# USB-HOST.net
KiCad netlist of a schematic drawn in Altium Designer
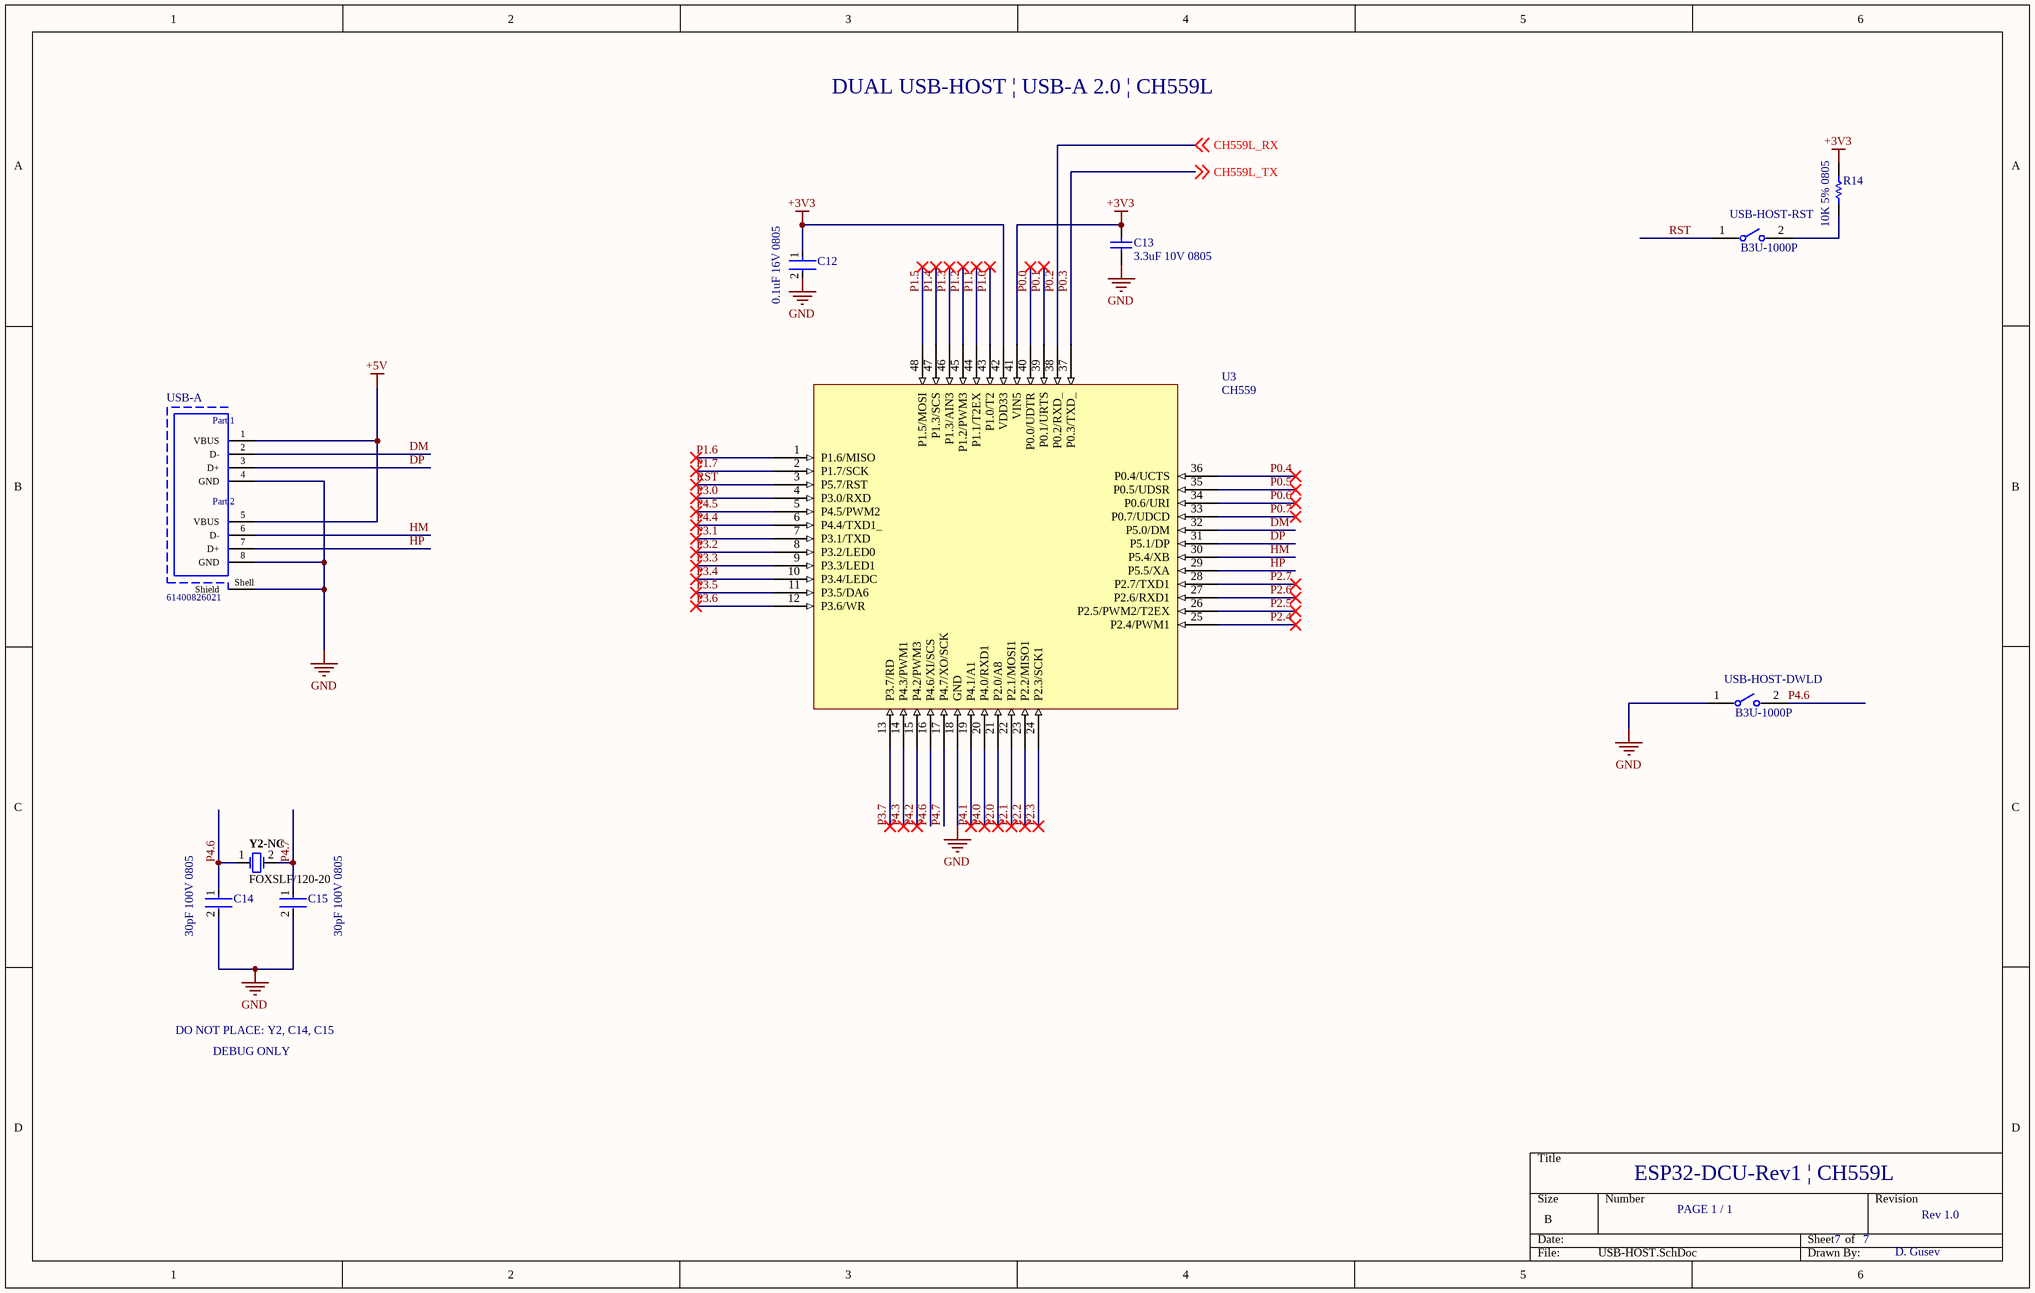
[diagram p0: USB-HOST.SchDoc]

(export (version "E")
  (design (tool "Eeschema 10.0.6"))
  (components
    (comp (ref "C12")
      (value "0.1uF 16V 0805")
      (footprint "FP-C0805C-DN-MFG")
      (description "CAP CER 0.1UF 50V X7R 0805")
      (fields
        (field (name "MANUFACTURER PART NUMBER") "C0805C104K5RACTU")
        (field (name "MANUFACTURER") "KEMET")
      )
      (libsource (lib "Altium Content Vault") (part "b4654b650e69147ec39a6b967a45e02"))
    )
    (comp (ref "C13")
      (value "3.3uF 10V 0805")
      (footprint "CAPC2013X140X50LL20T25")
      (fields
        (field (name "PART NUMBER") "0805ZD335KAT2A")
        (field (name "MANUFACTURER") "AVX Interconnect / Elco")
      )
      (libsource (lib "Altium Content Vault") (part "CAP"))
    )
    (comp (ref "C14")
      (value "30pF 100V 0805")
      (footprint "FP-C0805C-DN-MFG")
      (description "CAP CER 22PF 100V 5% NP0 0805")
      (fields
        (field (name "OCTOPART") "https://octopart.com/c0805c220j1gactu-kemet-3791395")
        (field (name "TOLERANCE") "0.05")
      )
      (libsource (lib "Altium Content Vault") (part "b4654b650e69147ec39a6b967a45e02"))
    )
    (comp (ref "C15")
      (value "30pF 100V 0805")
      (footprint "FP-C0805C-DN-MFG")
      (description "CAP CER 22PF 100V 5% NP0 0805")
      (fields
        (field (name "OCTOPART") "https://octopart.com/c0805c220j1gactu-kemet-3791395")
        (field (name "TOLERANCE") "0.05")
      )
      (libsource (lib "Altium Content Vault") (part "b4654b650e69147ec39a6b967a45e02"))
    )
    (comp (ref "R14")
      (value "10K 5% 0805")
      (footprint "RESC2013X60X40ML20T25")
      (fields (field (name "PART NUMBER") "ERA6AEB123V") (field (name "MANUFACTURER") "Panasonic"))
      (libsource (lib "Altium Content Vault") (part "RES"))
    )
    (comp (ref "U3")
      (value "CH559")
      (footprint "CH559L")
      (description "DUAL USB-HOST 2.0")
      (libsource (lib "ESP32-DCU-Rev1") (part "CH559"))
    )
    (comp (ref "USB-A")
      (value "61400826021")
      (footprint "61400826021")
      (description "USB 2.0 Type A Receptacle WR-COM, Stacked Horizontal, THT")
      (fields (field (name "MANUFACTURER") "Wurth Elektronik") (field (name "PUBLISHER") "WurthElektronik"))
      (libsource (lib "Altium Content Vault") (part "WE-USB-8-1SHLD"))
    )
    (comp (ref "USB-HOST-DWLD")
      (value "B3U-1000P")
      (footprint "FP-B3U-1000P-MFG")
      (description "SWITCH TACTILE SPST-NO 0.05A 12V")
      (libsource (lib "Altium Content Vault") (part "ae622034201233ca1abcedc05908f33"))
    )
    (comp (ref "USB-HOST-RST")
      (value "B3U-1000P")
      (footprint "FP-B3U-1000P-MFG")
      (description "SWITCH TACTILE SPST-NO 0.05A 12V")
      (libsource (lib "Altium Content Vault") (part "ae622034201233ca1abcedc05908f33"))
    )
    (comp (ref "Y2-NC")
      (value "FOXSLF/120-20")
      (footprint "FOX-FOXSLF-2_V")
      (description "Resistance Weld Thru-Hole Crystal, 12 MHz, +/-30 ppm, -20 to 70 degC, 2-Pin THD, RoHS, Bulk")
      (libsource (lib "Altium Content Vault") (part "XTAL-1-2-2"))
    )
  )
  (nets
    (net (code "1") (name "+3V3") (class "Default")
      (node (ref "C12") (pin "1") (pinfunction "1_1") (pintype "passive"))
      (node (ref "C13") (pin "2") (pinfunction "2_2") (pintype "passive"))
      (node (ref "R14") (pin "2") (pinfunction "2_2") (pintype "passive"))
      (node (ref "U3") (pin "41") (pinfunction "VIN5_41") (pintype "input"))
      (node (ref "U3") (pin "42") (pinfunction "VDD33_42") (pintype "input"))
    )
    (net (code "2") (name "+5V") (class "Default")
      (node (ref "USB-A") (pin "1") (pinfunction "VBUS_1") (pintype "passive"))
      (node (ref "USB-A") (pin "5") (pinfunction "VBUS_5") (pintype "passive"))
    )
    (net (code "3") (name "/DM") (class "Default")
      (node (ref "U3") (pin "32") (pinfunction "P5.0/DM_32") (pintype "input"))
      (node (ref "USB-A") (pin "2") (pinfunction "D-_2") (pintype "passive"))
    )
    (net (code "4") (name "/DP") (class "Default")
      (node (ref "U3") (pin "31") (pinfunction "P5.1/DP_31") (pintype "input"))
      (node (ref "USB-A") (pin "3") (pinfunction "D+_3") (pintype "passive"))
    )
    (net (code "5") (name "/HM") (class "Default")
      (node (ref "U3") (pin "30") (pinfunction "P5.4/XB_30") (pintype "input"))
      (node (ref "USB-A") (pin "6") (pinfunction "D-_6") (pintype "passive"))
    )
    (net (code "6") (name "/HP") (class "Default")
      (node (ref "U3") (pin "29") (pinfunction "P5.5/XA_29") (pintype "input"))
      (node (ref "USB-A") (pin "7") (pinfunction "D+_7") (pintype "passive"))
    )
    (net (code "7") (name "/P0.0") (class "Default")
      (node (ref "U3") (pin "40") (pinfunction "P0.0/UDTR_40") (pintype "input+no_connect"))
    )
    (net (code "8") (name "/P0.1") (class "Default")
      (node (ref "U3") (pin "39") (pinfunction "P0.1/URTS_39") (pintype "input+no_connect"))
    )
    (net (code "9") (name "/P0.4") (class "Default")
      (node (ref "U3") (pin "36") (pinfunction "P0.4/UCTS_36") (pintype "input+no_connect"))
    )
    (net (code "10") (name "/P0.5") (class "Default")
      (node (ref "U3") (pin "35") (pinfunction "P0.5/UDSR_35") (pintype "input+no_connect"))
    )
    (net (code "11") (name "/P0.6") (class "Default")
      (node (ref "U3") (pin "34") (pinfunction "P0.6/URI_34") (pintype "input+no_connect"))
    )
    (net (code "12") (name "/P0.7") (class "Default")
      (node (ref "U3") (pin "33") (pinfunction "P0.7/UDCD_33") (pintype "input+no_connect"))
    )
    (net (code "13") (name "/P1.0") (class "Default")
      (node (ref "U3") (pin "43") (pinfunction "P1.0/T2_43") (pintype "input+no_connect"))
    )
    (net (code "14") (name "/P1.1") (class "Default")
      (node (ref "U3") (pin "44") (pinfunction "P1.1/T2EX_44") (pintype "input+no_connect"))
    )
    (net (code "15") (name "/P1.2") (class "Default")
      (node (ref "U3") (pin "45") (pinfunction "P1.2/PWM3_45") (pintype "input+no_connect"))
    )
    (net (code "16") (name "/P1.3") (class "Default")
      (node (ref "U3") (pin "46") (pinfunction "P1.3/AIN3_46") (pintype "input+no_connect"))
    )
    (net (code "17") (name "/P1.4") (class "Default")
      (node (ref "U3") (pin "47") (pinfunction "P1.3/SCS_47") (pintype "input+no_connect"))
    )
    (net (code "18") (name "/P1.5") (class "Default")
      (node (ref "U3") (pin "48") (pinfunction "P1.5/MOSI_48") (pintype "input+no_connect"))
    )
    (net (code "19") (name "/P1.6") (class "Default")
      (node (ref "U3") (pin "1") (pinfunction "P1.6/MISO_1") (pintype "input+no_connect"))
    )
    (net (code "20") (name "/P1.7") (class "Default")
      (node (ref "U3") (pin "2") (pinfunction "P1.7/SCK_2") (pintype "input+no_connect"))
    )
    (net (code "21") (name "/P2.0") (class "Default")
      (node (ref "U3") (pin "21") (pinfunction "P2.0/A8_21") (pintype "input+no_connect"))
    )
    (net (code "22") (name "/P2.1") (class "Default")
      (node (ref "U3") (pin "22") (pinfunction "P2.1/MOSI1_22") (pintype "input+no_connect"))
    )
    (net (code "23") (name "/P2.2") (class "Default")
      (node (ref "U3") (pin "23") (pinfunction "P2.2/MISO1_23") (pintype "input+no_connect"))
    )
    (net (code "24") (name "/P2.3") (class "Default")
      (node (ref "U3") (pin "24") (pinfunction "P2.3/SCK1_24") (pintype "input+no_connect"))
    )
    (net (code "25") (name "/P2.4") (class "Default")
      (node (ref "U3") (pin "25") (pinfunction "P2.4/PWM1_25") (pintype "input+no_connect"))
    )
    (net (code "26") (name "/P2.5") (class "Default")
      (node (ref "U3") (pin "26") (pinfunction "P2.5/PWM2/T2EX_26") (pintype "input+no_connect"))
    )
    (net (code "27") (name "/P2.6") (class "Default")
      (node (ref "U3") (pin "27") (pinfunction "P2.6/RXD1_27") (pintype "input+no_connect"))
    )
    (net (code "28") (name "/P2.7") (class "Default")
      (node (ref "U3") (pin "28") (pinfunction "P2.7/TXD1_28") (pintype "input+no_connect"))
    )
    (net (code "29") (name "/P3.0") (class "Default")
      (node (ref "U3") (pin "4") (pinfunction "P3.0/RXD_4") (pintype "input+no_connect"))
    )
    (net (code "30") (name "/P3.1") (class "Default")
      (node (ref "U3") (pin "7") (pinfunction "P3.1/TXD_7") (pintype "input+no_connect"))
    )
    (net (code "31") (name "/P3.2") (class "Default")
      (node (ref "U3") (pin "8") (pinfunction "P3.2/LED0_8") (pintype "input+no_connect"))
    )
    (net (code "32") (name "/P3.3") (class "Default")
      (node (ref "U3") (pin "9") (pinfunction "P3.3/LED1_9") (pintype "input+no_connect"))
    )
    (net (code "33") (name "/P3.4") (class "Default")
      (node (ref "U3") (pin "10") (pinfunction "P3.4/LEDC_10") (pintype "input+no_connect"))
    )
    (net (code "34") (name "/P3.5") (class "Default")
      (node (ref "U3") (pin "11") (pinfunction "P3.5/DA6_11") (pintype "input+no_connect"))
    )
    (net (code "35") (name "/P3.6") (class "Default")
      (node (ref "U3") (pin "12") (pinfunction "P3.6/WR_12") (pintype "input+no_connect"))
    )
    (net (code "36") (name "/P3.7") (class "Default")
      (node (ref "U3") (pin "13") (pinfunction "P3.7/RD_13") (pintype "input+no_connect"))
    )
    (net (code "37") (name "/P4.0") (class "Default")
      (node (ref "U3") (pin "20") (pinfunction "P4.0/RXD1_20") (pintype "input+no_connect"))
    )
    (net (code "38") (name "/P4.1") (class "Default")
      (node (ref "U3") (pin "19") (pinfunction "P4.1/A1_19") (pintype "input+no_connect"))
    )
    (net (code "39") (name "/P4.2") (class "Default")
      (node (ref "U3") (pin "15") (pinfunction "P4.2/PWM3_15") (pintype "input+no_connect"))
    )
    (net (code "40") (name "/P4.3") (class "Default")
      (node (ref "U3") (pin "14") (pinfunction "P4.3/PWM1_14") (pintype "input+no_connect"))
    )
    (net (code "41") (name "/P4.4") (class "Default")
      (node (ref "U3") (pin "6") (pinfunction "P4.4/TXD1__6") (pintype "input+no_connect"))
    )
    (net (code "42") (name "/P4.5") (class "Default")
      (node (ref "U3") (pin "5") (pinfunction "P4.5/PWM2_5") (pintype "input+no_connect"))
    )
    (net (code "43") (name "/P4.6") (class "Default")
      (node (ref "C14") (pin "1") (pinfunction "1_1") (pintype "passive"))
      (node (ref "U3") (pin "16") (pinfunction "P4.6/XI/SCS_16") (pintype "input"))
      (node (ref "USB-HOST-DWLD") (pin "2") (pinfunction "2_2") (pintype "passive"))
      (node (ref "Y2-NC") (pin "1") (pinfunction "1_1") (pintype "passive"))
    )
    (net (code "44") (name "/P4.7") (class "Default")
      (node (ref "C15") (pin "1") (pinfunction "1_1") (pintype "passive"))
      (node (ref "U3") (pin "17") (pinfunction "P4.7/XO/SCK_17") (pintype "input"))
      (node (ref "Y2-NC") (pin "2") (pinfunction "2_2") (pintype "passive"))
    )
    (net (code "45") (name "/RST") (class "Default")
      (node (ref "U3") (pin "3") (pinfunction "P5.7/RST_3") (pintype "input"))
      (node (ref "USB-HOST-RST") (pin "1") (pinfunction "1_1") (pintype "passive"))
    )
    (net (code "46") (name "CH559L_RX") (class "Default")
      (node (ref "U3") (pin "38") (pinfunction "P0.2/RXD__38") (pintype "input"))
    )
    (net (code "47") (name "CH559L_TX") (class "Default")
      (node (ref "U3") (pin "37") (pinfunction "P0.3/TXD__37") (pintype "input"))
    )
    (net (code "48") (name "GND") (class "Default")
      (node (ref "C12") (pin "2") (pinfunction "2_2") (pintype "passive"))
      (node (ref "C13") (pin "1") (pinfunction "1_1") (pintype "passive"))
      (node (ref "C14") (pin "2") (pinfunction "2_2") (pintype "passive"))
      (node (ref "C15") (pin "2") (pinfunction "2_2") (pintype "passive"))
      (node (ref "U3") (pin "18") (pinfunction "GND_18") (pintype "input"))
      (node (ref "USB-A") (pin "4") (pinfunction "GND_4") (pintype "passive"))
      (node (ref "USB-A") (pin "8") (pinfunction "GND_8") (pintype "passive"))
      (node (ref "USB-A") (pin "Shell") (pinfunction "Shield_Shell") (pintype "passive"))
      (node (ref "USB-HOST-DWLD") (pin "1") (pinfunction "1_1") (pintype "passive"))
    )
    (net (code "49") (name "Net-(R14-Pad1)") (class "Default")
      (node (ref "R14") (pin "1") (pinfunction "1_1") (pintype "passive"))
      (node (ref "USB-HOST-RST") (pin "2") (pinfunction "2_2") (pintype "passive"))
    )
  )
)
